# SCH_NFC-card_2024-04-14.net
KiCad netlist of a schematic drawn in EasyEDA
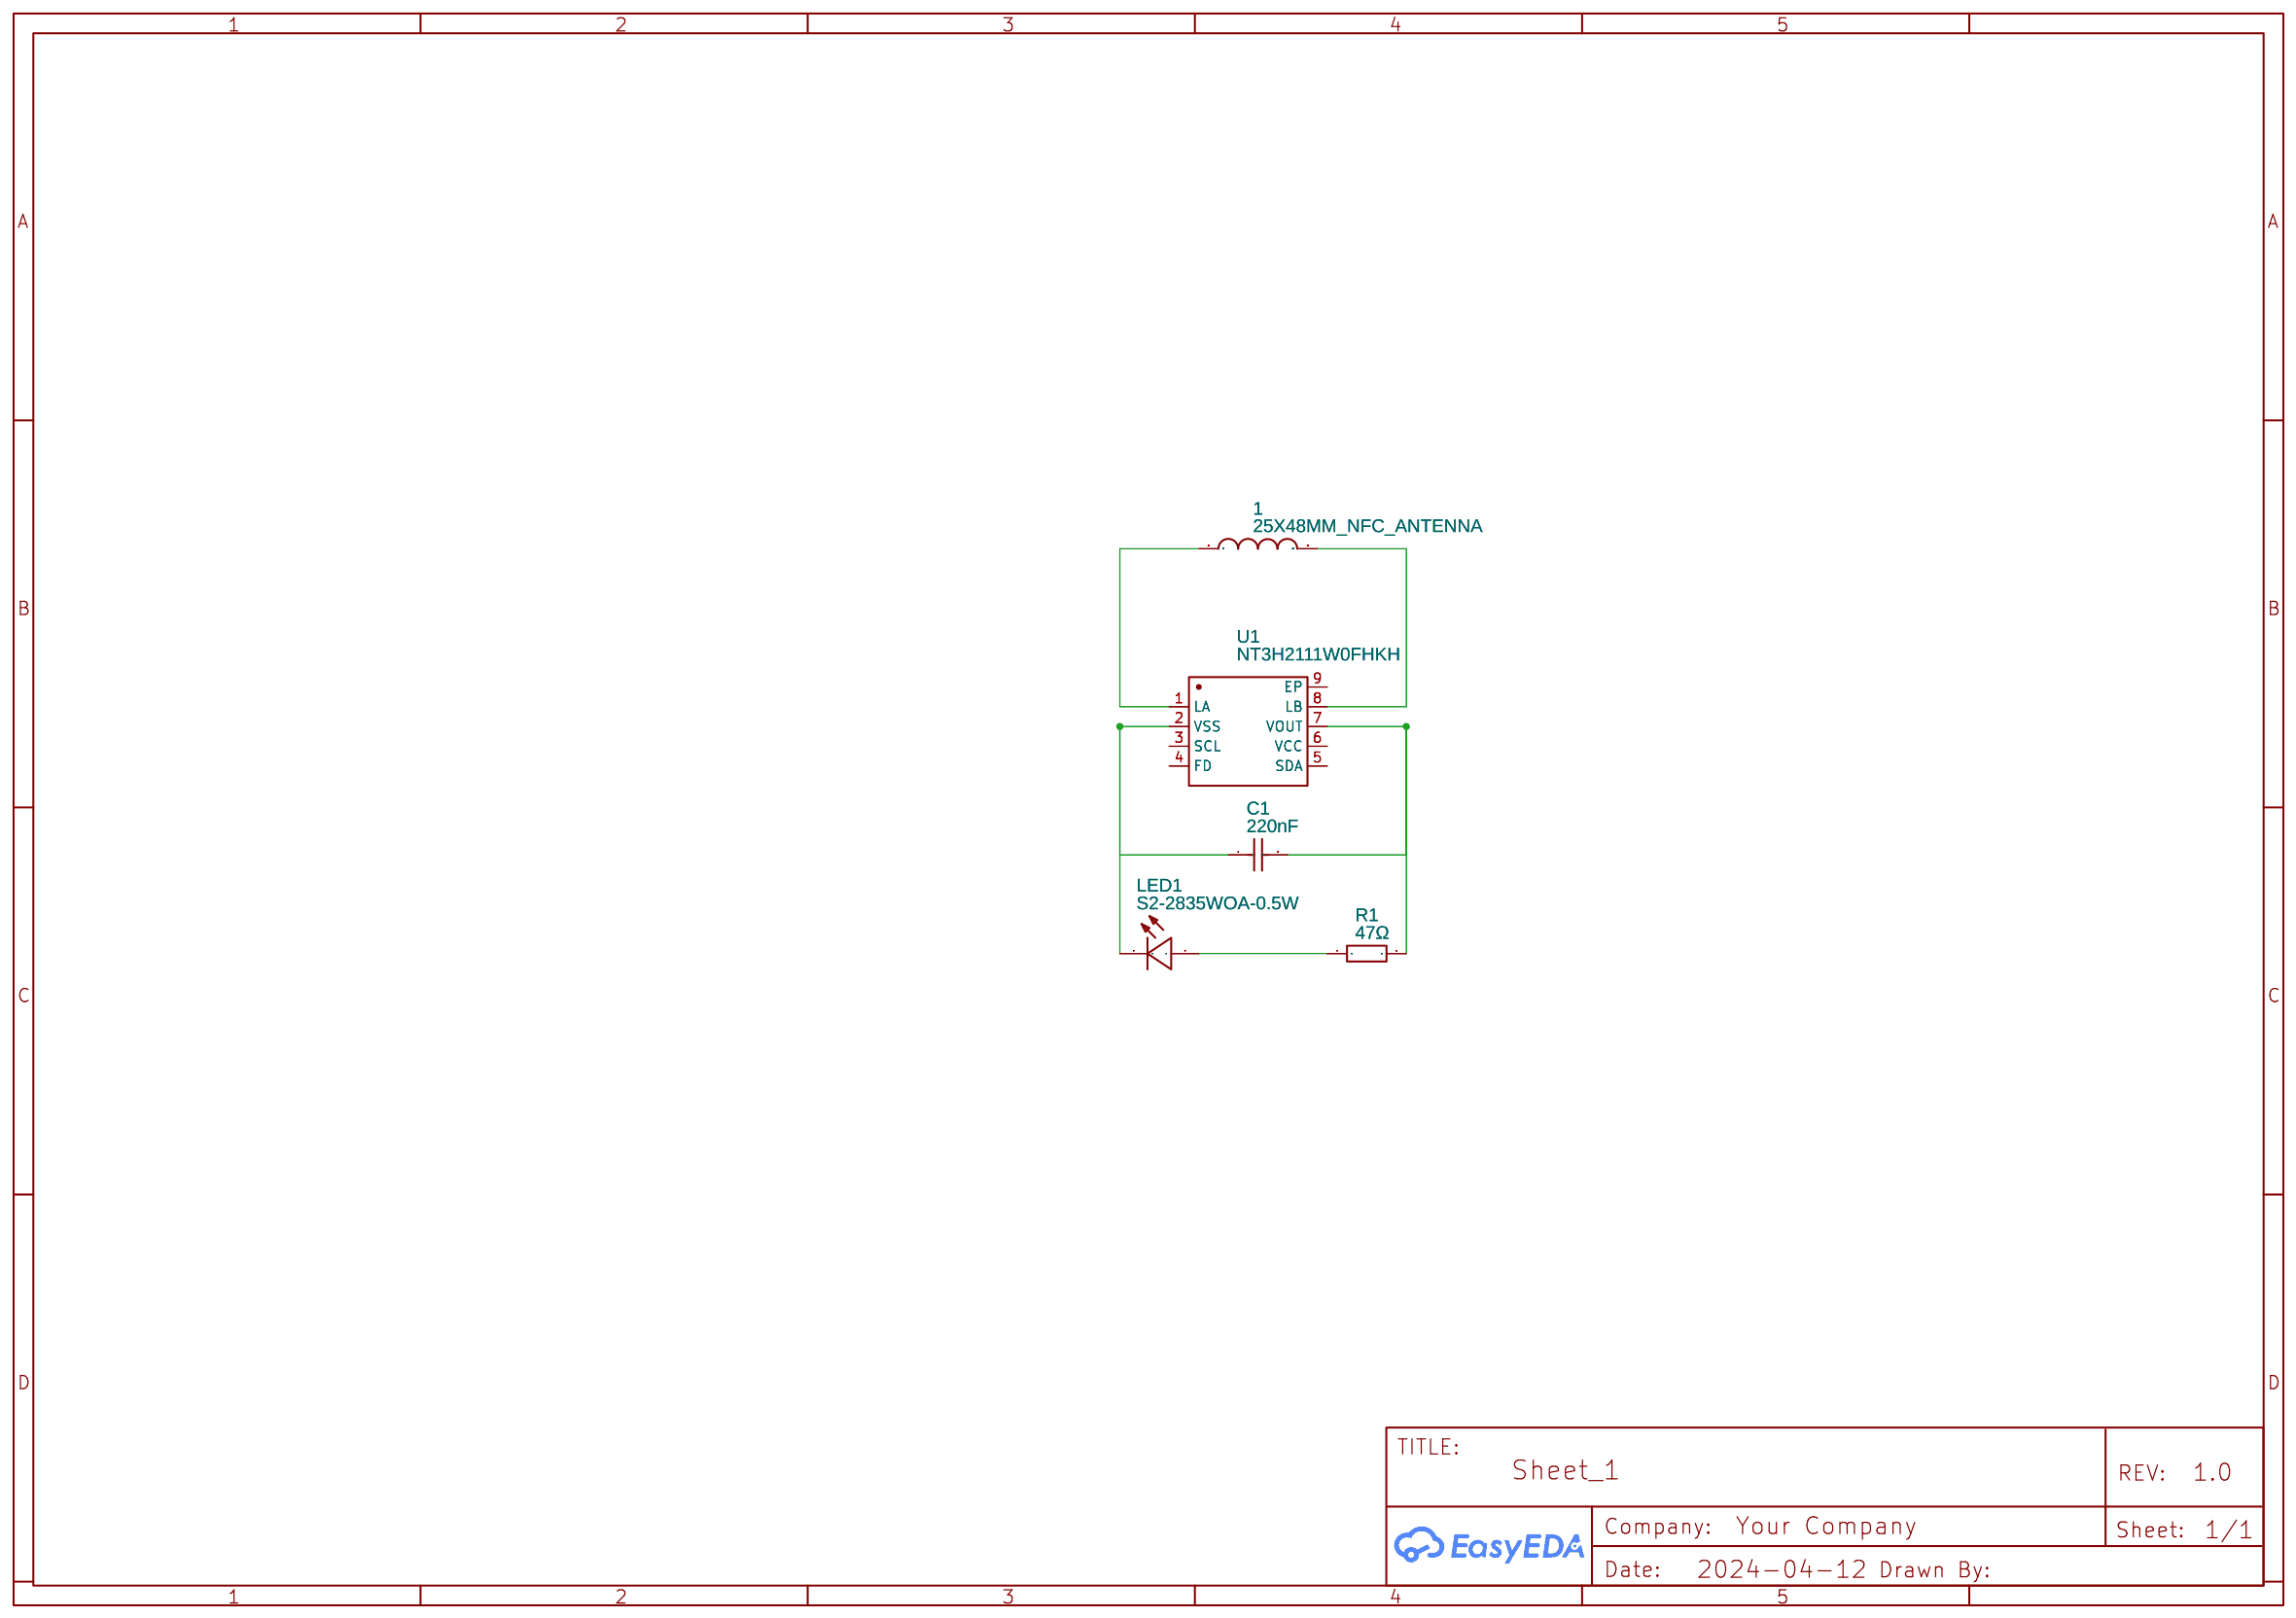
[diagram p0: schematic sheet]

(export (version "E")
  (design (tool "Eeschema 10.0.6"))
  (components
    (comp (ref "1") (value "25X48MM_NFC_ANTENNA") (libsource (lib "") (part "25X48MM_NFC_ANTENNA")))
    (comp (ref "C1")
      (value "220nF")
      (fields
        (field (name "Manufacturer Part") "GRM155R61A224KE19D")
        (field (name "Manufacturer") "muRata(村田)")
      )
      (libsource (lib "") (part "GRM155R61A224KE19D"))
    )
    (comp (ref "LED1") (value "S2-2835WOA-0.5W") (libsource (lib "") (part "S2-2835WOA-0.5W")))
    (comp (ref "R1")
      (value "47Ω")
      (fields
        (field (name "Manufacturer Part") "0603WAF470JT5E")
        (field (name "Manufacturer") "UNI-ROYAL(厚声)")
      )
      (libsource (lib "") (part "0603WAF470JT5E"))
    )
    (comp (ref "U1")
      (value "NT3H2111W0FHKH")
      (fields (field (name "Manufacturer") "NXP(恩智浦)"))
      (libsource (lib "") (part "NT3H2111W0FHKH"))
    )
  )
  (nets
    (net (code "1") (name "Net-(LED1-A)") (class "Default")
      (node (ref "LED1") (pin "2") (pinfunction "A_2") (pintype "unspecified"))
      (node (ref "R1") (pin "1") (pinfunction "1_1") (pintype "input"))
    )
    (net (code "2") (name "Net-(LED1-K)") (class "Default")
      (node (ref "C1") (pin "1") (pinfunction "1_1") (pintype "input"))
      (node (ref "LED1") (pin "1") (pinfunction "K_1") (pintype "unspecified"))
      (node (ref "U1") (pin "2") (pinfunction "VSS_2") (pintype "unspecified"))
    )
    (net (code "3") (name "Net-(U1-LA)") (class "Default")
      (node (ref "1") (pin "P$1") (pinfunction "P$1_P$1") (pintype "bidirectional"))
      (node (ref "U1") (pin "1") (pinfunction "LA_1") (pintype "unspecified"))
    )
    (net (code "4") (name "Net-(U1-LB)") (class "Default")
      (node (ref "1") (pin "P$2") (pinfunction "P$2_P$2") (pintype "bidirectional"))
      (node (ref "U1") (pin "8") (pinfunction "LB_8") (pintype "unspecified"))
    )
    (net (code "5") (name "Net-(U1-VOUT)") (class "Default")
      (node (ref "C1") (pin "2") (pinfunction "2_2") (pintype "input"))
      (node (ref "R1") (pin "2") (pinfunction "2_2") (pintype "input"))
      (node (ref "U1") (pin "7") (pinfunction "VOUT_7") (pintype "unspecified"))
    )
    (net (code "6") (name "unconnected-(U1-EP-Pad9)") (class "Default")
      (node (ref "U1") (pin "9") (pinfunction "EP_9") (pintype "unspecified"))
    )
    (net (code "7") (name "unconnected-(U1-FD-Pad4)") (class "Default")
      (node (ref "U1") (pin "4") (pinfunction "FD_4") (pintype "unspecified"))
    )
    (net (code "8") (name "unconnected-(U1-SCL-Pad3)") (class "Default")
      (node (ref "U1") (pin "3") (pinfunction "SCL_3") (pintype "unspecified"))
    )
    (net (code "9") (name "unconnected-(U1-SDA-Pad5)") (class "Default")
      (node (ref "U1") (pin "5") (pinfunction "SDA_5") (pintype "unspecified"))
    )
    (net (code "10") (name "unconnected-(U1-VCC-Pad6)") (class "Default")
      (node (ref "U1") (pin "6") (pinfunction "VCC_6") (pintype "unspecified"))
    )
  )
)
